# 301_GridPos3.net
KiCad netlist of a schematic drawn in Altium Designer
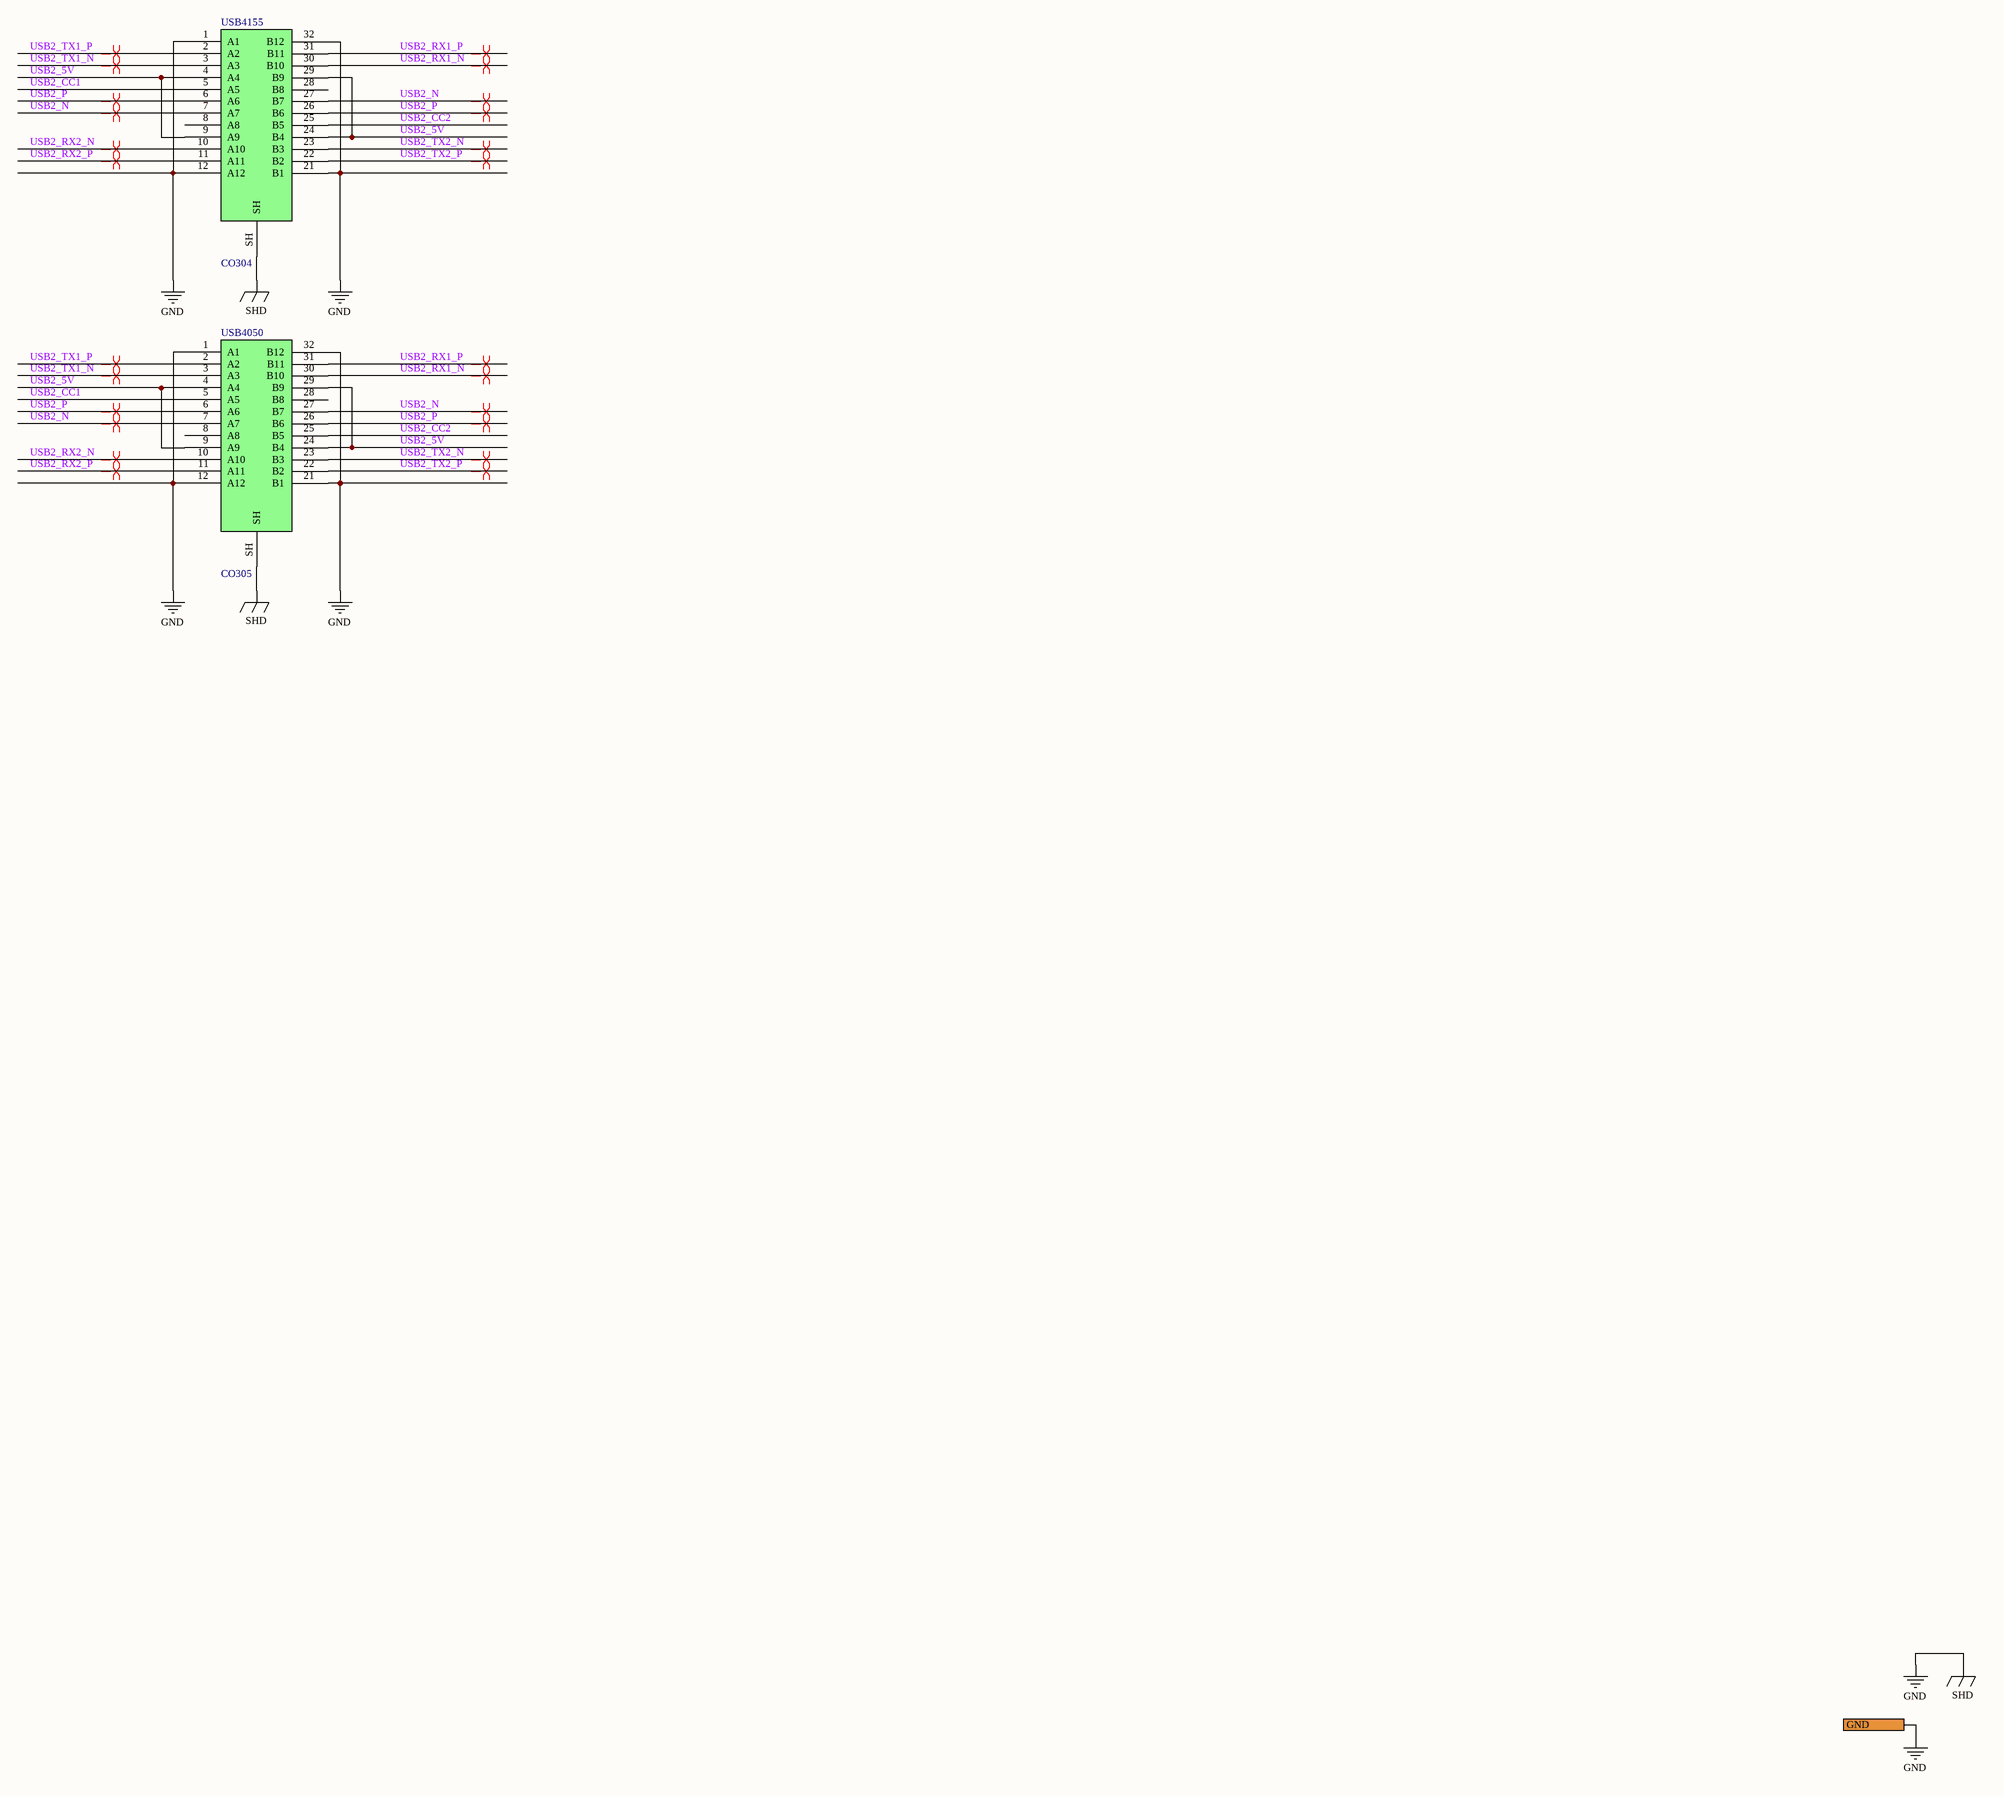
[diagram p0: 301_GridPos3.SchDoc]

(export (version "E")
  (design (tool "Eeschema 10.0.6"))
  (components
    (comp (ref "CO304")
      (value "USB4155")
      (footprint "USB4155-03-C")
      (description "USB C connector Plug Horizontal")
      (fields
        (field (name "REFVAL") "USB4155")
        (field (name "PART NUMBER") "CO0031")
        (field (name "MANFACTPART") "USB4155-03-C")
      )
      (libsource (lib "GTS_Database") (part "USB-CC"))
    )
    (comp (ref "CO305")
      (value "USB4050")
      (footprint "USB4050-30-A")
      (description "USB C connector Receptacle Horizontal")
      (fields
        (field (name "REFVAL") "USB4050")
        (field (name "PART NUMBER") "CO0039")
        (field (name "MANFACTPART") "USB4050-30-A")
      )
      (libsource (lib "GTS_Database") (part "USB-CC"))
    )
  )
  (nets
    (net (code "1") (name "/USB2_5V") (class "Default")
      (node (ref "CO304") (pin "24") (pinfunction "B4_24") (pintype "passive"))
      (node (ref "CO304") (pin "29") (pinfunction "B9_29") (pintype "passive"))
      (node (ref "CO304") (pin "4") (pinfunction "A4_4") (pintype "passive"))
      (node (ref "CO304") (pin "9") (pinfunction "A9_9") (pintype "passive"))
      (node (ref "CO305") (pin "24") (pinfunction "B4_24") (pintype "passive"))
      (node (ref "CO305") (pin "29") (pinfunction "B9_29") (pintype "passive"))
      (node (ref "CO305") (pin "4") (pinfunction "A4_4") (pintype "passive"))
      (node (ref "CO305") (pin "9") (pinfunction "A9_9") (pintype "passive"))
    )
    (net (code "2") (name "/USB2_CC1") (class "Default")
      (node (ref "CO304") (pin "5") (pinfunction "A5_5") (pintype "passive"))
      (node (ref "CO305") (pin "5") (pinfunction "A5_5") (pintype "passive"))
    )
    (net (code "3") (name "/USB2_CC2") (class "Default")
      (node (ref "CO304") (pin "25") (pinfunction "B5_25") (pintype "passive"))
      (node (ref "CO305") (pin "25") (pinfunction "B5_25") (pintype "passive"))
    )
    (net (code "4") (name "/USB2_N") (class "Default")
      (node (ref "CO304") (pin "27") (pinfunction "B7_27") (pintype "passive"))
      (node (ref "CO304") (pin "7") (pinfunction "A7_7") (pintype "passive"))
      (node (ref "CO305") (pin "27") (pinfunction "B7_27") (pintype "passive"))
      (node (ref "CO305") (pin "7") (pinfunction "A7_7") (pintype "passive"))
    )
    (net (code "5") (name "/USB2_P") (class "Default")
      (node (ref "CO304") (pin "26") (pinfunction "B6_26") (pintype "passive"))
      (node (ref "CO304") (pin "6") (pinfunction "A6_6") (pintype "passive"))
      (node (ref "CO305") (pin "26") (pinfunction "B6_26") (pintype "passive"))
      (node (ref "CO305") (pin "6") (pinfunction "A6_6") (pintype "passive"))
    )
    (net (code "6") (name "/USB2_RX1_N") (class "Default")
      (node (ref "CO304") (pin "30") (pinfunction "B10_30") (pintype "passive"))
      (node (ref "CO305") (pin "30") (pinfunction "B10_30") (pintype "passive"))
    )
    (net (code "7") (name "/USB2_RX1_P") (class "Default")
      (node (ref "CO304") (pin "31") (pinfunction "B11_31") (pintype "passive"))
      (node (ref "CO305") (pin "31") (pinfunction "B11_31") (pintype "passive"))
    )
    (net (code "8") (name "/USB2_RX2_N") (class "Default")
      (node (ref "CO304") (pin "10") (pinfunction "A10_10") (pintype "passive"))
      (node (ref "CO305") (pin "10") (pinfunction "A10_10") (pintype "passive"))
    )
    (net (code "9") (name "/USB2_RX2_P") (class "Default")
      (node (ref "CO304") (pin "11") (pinfunction "A11_11") (pintype "passive"))
      (node (ref "CO305") (pin "11") (pinfunction "A11_11") (pintype "passive"))
    )
    (net (code "10") (name "/USB2_TX1_N") (class "Default")
      (node (ref "CO304") (pin "3") (pinfunction "A3_3") (pintype "passive"))
      (node (ref "CO305") (pin "3") (pinfunction "A3_3") (pintype "passive"))
    )
    (net (code "11") (name "/USB2_TX1_P") (class "Default")
      (node (ref "CO304") (pin "2") (pinfunction "A2_2") (pintype "passive"))
      (node (ref "CO305") (pin "2") (pinfunction "A2_2") (pintype "passive"))
    )
    (net (code "12") (name "/USB2_TX2_N") (class "Default")
      (node (ref "CO304") (pin "23") (pinfunction "B3_23") (pintype "passive"))
      (node (ref "CO305") (pin "23") (pinfunction "B3_23") (pintype "passive"))
    )
    (net (code "13") (name "/USB2_TX2_P") (class "Default")
      (node (ref "CO304") (pin "22") (pinfunction "B2_22") (pintype "passive"))
      (node (ref "CO305") (pin "22") (pinfunction "B2_22") (pintype "passive"))
    )
    (net (code "14") (name "GND") (class "Default")
      (node (ref "CO304") (pin "1") (pinfunction "A1_1") (pintype "passive"))
      (node (ref "CO304") (pin "12") (pinfunction "A12_12") (pintype "passive"))
      (node (ref "CO304") (pin "21") (pinfunction "B1_21") (pintype "passive"))
      (node (ref "CO304") (pin "32") (pinfunction "B12_32") (pintype "passive"))
      (node (ref "CO304") (pin "SH") (pinfunction "SH_SH") (pintype "power_in"))
      (node (ref "CO305") (pin "1") (pinfunction "A1_1") (pintype "passive"))
      (node (ref "CO305") (pin "12") (pinfunction "A12_12") (pintype "passive"))
      (node (ref "CO305") (pin "21") (pinfunction "B1_21") (pintype "passive"))
      (node (ref "CO305") (pin "32") (pinfunction "B12_32") (pintype "passive"))
      (node (ref "CO305") (pin "SH") (pinfunction "SH_SH") (pintype "power_in"))
    )
    (net (code "15") (name "unconnected-(CO304-A8-Pad8)") (class "Default")
      (node (ref "CO304") (pin "8") (pinfunction "A8_8") (pintype "passive"))
    )
    (net (code "16") (name "unconnected-(CO304-B8-Pad28)") (class "Default")
      (node (ref "CO304") (pin "28") (pinfunction "B8_28") (pintype "passive"))
    )
    (net (code "17") (name "unconnected-(CO305-A8-Pad8)") (class "Default")
      (node (ref "CO305") (pin "8") (pinfunction "A8_8") (pintype "passive"))
    )
    (net (code "18") (name "unconnected-(CO305-B8-Pad28)") (class "Default")
      (node (ref "CO305") (pin "28") (pinfunction "B8_28") (pintype "passive"))
    )
  )
)
